# RFTransceiver.net
KiCad netlist of a schematic drawn in Altium Designer
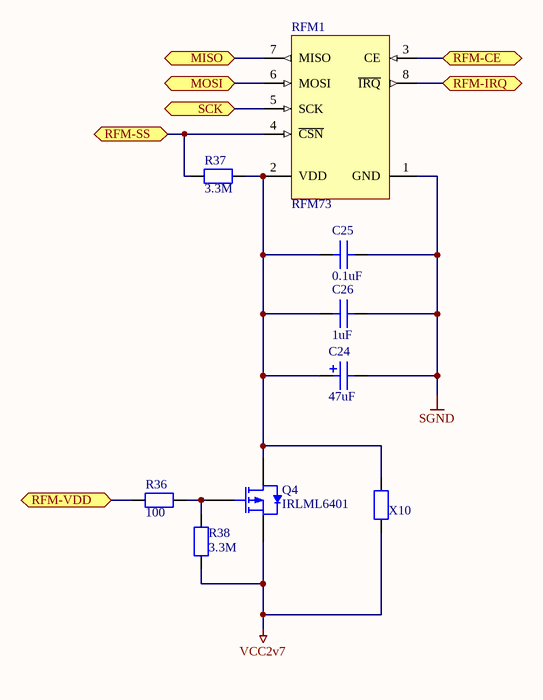
[diagram p0: RFTransceiver.SchDoc]

(export (version "E")
  (design (tool "Eeschema 10.0.6"))
  (components
    (comp (ref "C24")
      (value "47uF")
      (footprint "TC2917")
      (description "C47uF-10V-tant")
      (fields (field (name "VOLTAGE") "10V"))
      (libsource (lib "MCounter_Common") (part "C47uF-10V-tant"))
    )
    (comp (ref "C25")
      (value "0.1uF")
      (footprint "C0805")
      (description "C0.1uF-50V")
      (fields (field (name "VOLTAGE") "50V"))
      (libsource (lib "MCounter_Common") (part "C0.1uF-50V"))
    )
    (comp (ref "C26")
      (value "1uF")
      (footprint "C0805")
      (description "C1uF-50V")
      (fields (field (name "VOLTAGE") "50V"))
      (libsource (lib "MCounter_Common") (part "C1uF-50V"))
    )
    (comp (ref "Q4")
      (value "IRLML6401")
      (footprint "SOT23_N")
      (description "P-Channel Power MOSFET")
      (libsource (lib "MCounter_Common") (part "IRLML6401"))
    )
    (comp (ref "R36")
      (value "100")
      (footprint "R0805")
      (description "R-100-5%")
      (fields (field (name "Comment") "R100-5%"))
      (libsource (lib "MCounter_Common") (part "R100-5%"))
    )
    (comp (ref "R37")
      (value "3.3M")
      (footprint "R0805")
      (description "R3.3M-5%")
      (libsource (lib "MCounter_Common") (part "R3.3M-5%"))
    )
    (comp (ref "R38")
      (value "3.3M")
      (footprint "R0805")
      (description "R3.3M-5%")
      (libsource (lib "") (part "R3.3M-5%_1"))
    )
    (comp (ref "RFM1")
      (value "RFM73")
      (footprint "RFM73-SML")
      (description "2.4GHz GFSK Transceiver")
      (libsource (lib "Chips") (part "RFM73"))
    )
    (comp (ref "X10")
      (value "JUMPER0")
      (footprint "R0805")
      (libsource (lib "MCounter_Common") (part "JUMPER0"))
    )
  )
  (nets
    (net (code "1") (name "/MISO") (class "Default")
      (node (ref "RFM1") (pin "7") (pinfunction "MISO_7") (pintype "output"))
    )
    (net (code "2") (name "/MOSI") (class "Default")
      (node (ref "RFM1") (pin "6") (pinfunction "MOSI_6") (pintype "input"))
    )
    (net (code "3") (name "/RFM-CE") (class "Default")
      (node (ref "RFM1") (pin "3") (pinfunction "CE_3") (pintype "input"))
    )
    (net (code "4") (name "/RFM-IRQ") (class "Default")
      (node (ref "RFM1") (pin "8") (pinfunction "~{IRQ}_8") (pintype "output"))
    )
    (net (code "5") (name "/RFM-SS") (class "Default")
      (node (ref "R37") (pin "2") (pinfunction "2_2") (pintype "passive"))
      (node (ref "RFM1") (pin "4") (pinfunction "~{CSN}_4") (pintype "input"))
    )
    (net (code "6") (name "/RFM-VDD") (class "Default")
      (node (ref "R36") (pin "1") (pinfunction "1_1") (pintype "passive"))
    )
    (net (code "7") (name "/SCK") (class "Default")
      (node (ref "RFM1") (pin "5") (pinfunction "SCK_5") (pintype "input"))
    )
    (net (code "8") (name "Net-(Q4-D)") (class "Default")
      (node (ref "C24") (pin "1") (pinfunction "1_1") (pintype "passive"))
      (node (ref "C25") (pin "1") (pinfunction "1_1") (pintype "passive"))
      (node (ref "C26") (pin "1") (pinfunction "1_1") (pintype "passive"))
      (node (ref "Q4") (pin "3") (pinfunction "D_3") (pintype "passive"))
      (node (ref "R37") (pin "1") (pinfunction "1_1") (pintype "passive"))
      (node (ref "RFM1") (pin "2") (pinfunction "VDD_2") (pintype "power_in"))
      (node (ref "X10") (pin "2") (pinfunction "2_2") (pintype "passive"))
    )
    (net (code "9") (name "Net-(Q4-G)") (class "Default")
      (node (ref "Q4") (pin "1") (pinfunction "G_1") (pintype "passive"))
      (node (ref "R36") (pin "2") (pinfunction "2_2") (pintype "passive"))
      (node (ref "R38") (pin "1") (pinfunction "1_1") (pintype "passive"))
    )
    (net (code "10") (name "SGND") (class "Default")
      (node (ref "C24") (pin "2") (pinfunction "2_2") (pintype "passive"))
      (node (ref "C25") (pin "2") (pinfunction "2_2") (pintype "passive"))
      (node (ref "C26") (pin "2") (pinfunction "2_2") (pintype "passive"))
      (node (ref "RFM1") (pin "1") (pinfunction "GND_1") (pintype "power_in"))
    )
    (net (code "11") (name "VCC2v7") (class "Default")
      (node (ref "Q4") (pin "2") (pinfunction "S_2") (pintype "passive"))
      (node (ref "R38") (pin "2") (pinfunction "2_2") (pintype "passive"))
      (node (ref "X10") (pin "1") (pinfunction "1_1") (pintype "passive"))
    )
  )
)
